# MCU.net
KiCad netlist of a schematic drawn in Altium Designer
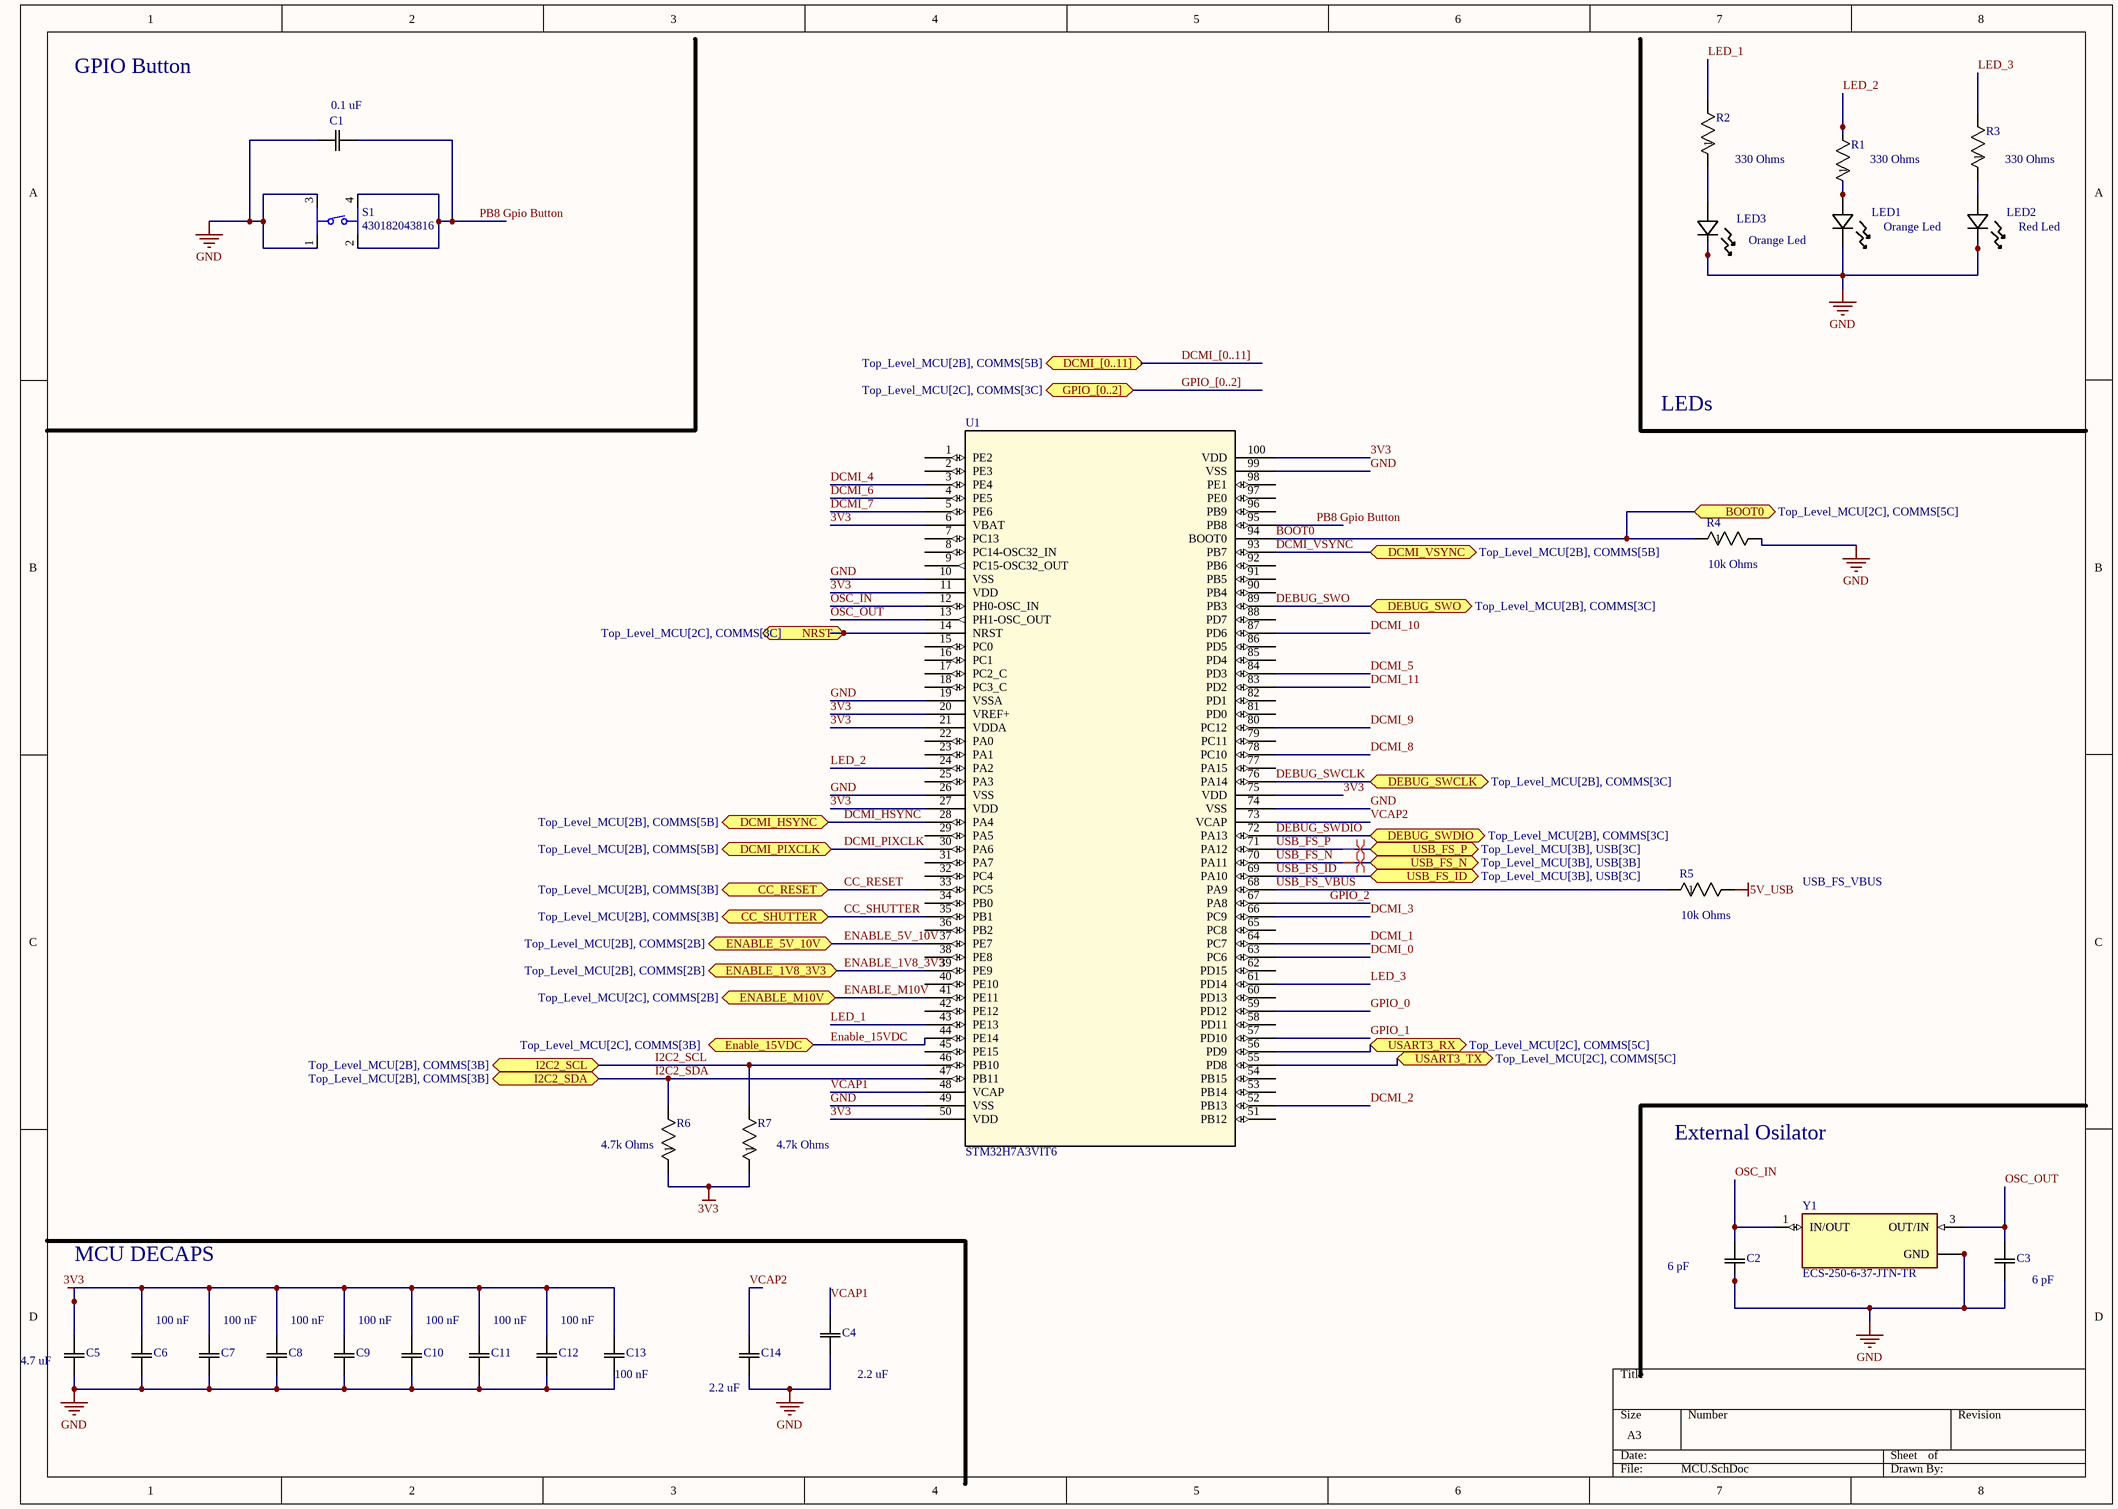
[diagram p0: MCU.SchDoc]

(export (version "E")
  (design (tool "Eeschema 10.0.6"))
  (components
    (comp (ref "C1")
      (value "CC0805KRX7R7BB104")
      (footprint "CC0805N_YAG")
      (description "Description")
      (fields (field (name "COPYRIGHT") "Copyright (C) 2025 Ultra Librarian. All rights reserved."))
      (libsource (lib "CC0805KRX7R7BB104") (part "CC0805KRX7R7BB104"))
    )
    (comp (ref "C2")
      (value "CC0805KRX7R7BB104")
      (footprint "CC0805N_YAG")
      (description "Description")
      (fields (field (name "COPYRIGHT") "Copyright (C) 2025 Ultra Librarian. All rights reserved."))
      (libsource (lib "CC0805KRX7R7BB104") (part "CC0805KRX7R7BB104"))
    )
    (comp (ref "C3")
      (value "CC0805KRX7R7BB104")
      (footprint "CC0805N_YAG")
      (description "Description")
      (fields (field (name "COPYRIGHT") "Copyright (C) 2025 Ultra Librarian. All rights reserved."))
      (libsource (lib "CC0805KRX7R7BB104") (part "CC0805KRX7R7BB104"))
    )
    (comp (ref "C4")
      (value "CC0805KRX7R7BB104")
      (footprint "CC0805N_YAG")
      (description "Description")
      (fields (field (name "COPYRIGHT") "Copyright (C) 2025 Ultra Librarian. All rights reserved."))
      (libsource (lib "CC0805KRX7R7BB104") (part "CC0805KRX7R7BB104"))
    )
    (comp (ref "C5")
      (value "CC0805KRX7R7BB104")
      (footprint "CC0805N_YAG")
      (description "Description")
      (fields (field (name "COPYRIGHT") "Copyright (C) 2025 Ultra Librarian. All rights reserved."))
      (libsource (lib "CC0805KRX7R7BB104") (part "CC0805KRX7R7BB104"))
    )
    (comp (ref "C6")
      (value "CC0805KRX7R7BB104")
      (footprint "CC0805N_YAG")
      (description "Description")
      (fields (field (name "COPYRIGHT") "Copyright (C) 2025 Ultra Librarian. All rights reserved."))
      (libsource (lib "CC0805KRX7R7BB104") (part "CC0805KRX7R7BB104"))
    )
    (comp (ref "C7")
      (value "CC0805KRX7R7BB104")
      (footprint "CC0805N_YAG")
      (description "Description")
      (fields (field (name "COPYRIGHT") "Copyright (C) 2025 Ultra Librarian. All rights reserved."))
      (libsource (lib "CC0805KRX7R7BB104") (part "CC0805KRX7R7BB104"))
    )
    (comp (ref "C8")
      (value "CC0805KRX7R7BB104")
      (footprint "CC0805N_YAG")
      (description "Description")
      (fields (field (name "COPYRIGHT") "Copyright (C) 2025 Ultra Librarian. All rights reserved."))
      (libsource (lib "CC0805KRX7R7BB104") (part "CC0805KRX7R7BB104"))
    )
    (comp (ref "C9")
      (value "CC0805KRX7R7BB104")
      (footprint "CC0805N_YAG")
      (description "Description")
      (fields (field (name "COPYRIGHT") "Copyright (C) 2025 Ultra Librarian. All rights reserved."))
      (libsource (lib "CC0805KRX7R7BB104") (part "CC0805KRX7R7BB104"))
    )
    (comp (ref "C10")
      (value "CC0805KRX7R7BB104")
      (footprint "CC0805N_YAG")
      (description "Description")
      (fields (field (name "COPYRIGHT") "Copyright (C) 2025 Ultra Librarian. All rights reserved."))
      (libsource (lib "CC0805KRX7R7BB104") (part "CC0805KRX7R7BB104"))
    )
    (comp (ref "C11")
      (value "CC0805KRX7R7BB104")
      (footprint "CC0805N_YAG")
      (description "Description")
      (fields (field (name "COPYRIGHT") "Copyright (C) 2025 Ultra Librarian. All rights reserved."))
      (libsource (lib "CC0805KRX7R7BB104") (part "CC0805KRX7R7BB104"))
    )
    (comp (ref "C12")
      (value "CC0805KRX7R7BB104")
      (footprint "CC0805N_YAG")
      (description "Description")
      (fields (field (name "COPYRIGHT") "Copyright (C) 2025 Ultra Librarian. All rights reserved."))
      (libsource (lib "CC0805KRX7R7BB104") (part "CC0805KRX7R7BB104"))
    )
    (comp (ref "C13")
      (value "CC0805KRX7R7BB104")
      (footprint "CC0805N_YAG")
      (description "Description")
      (fields (field (name "COPYRIGHT") "Copyright (C) 2025 Ultra Librarian. All rights reserved."))
      (libsource (lib "CC0805KRX7R7BB104") (part "CC0805KRX7R7BB104"))
    )
    (comp (ref "C14")
      (value "CC0805KRX7R7BB104")
      (footprint "CC0805N_YAG")
      (description "Description")
      (fields (field (name "COPYRIGHT") "Copyright (C) 2025 Ultra Librarian. All rights reserved."))
      (libsource (lib "CC0805KRX7R7BB104") (part "CC0805KRX7R7BB104"))
    )
    (comp (ref "LED1")
      (value "LTST-C170KFKT")
      (footprint "LED_LTST-C170KFKT_LTO")
      (description "Description")
      (fields (field (name "COPYRIGHT") "Copyright (C) 2025 Ultra Librarian. All rights reserved."))
      (libsource (lib "LTST-C170KFKT") (part "LTST-C170KFKT"))
    )
    (comp (ref "LED2")
      (value "LTST-C171KRKT")
      (footprint "LED_LTST-C171_LTO")
      (description "Description")
      (fields (field (name "COPYRIGHT") "Copyright (C) 2025 Ultra Librarian. All rights reserved."))
      (libsource (lib "LTST-C171KRKT") (part "LTST-C171KRKT"))
    )
    (comp (ref "LED3")
      (value "LTST-C170KFKT")
      (footprint "LED_LTST-C170KFKT_LTO")
      (description "Description")
      (fields (field (name "COPYRIGHT") "Copyright (C) 2025 Ultra Librarian. All rights reserved."))
      (libsource (lib "LTST-C170KFKT") (part "LTST-C170KFKT"))
    )
    (comp (ref "R1")
      (value "RC0805FR-074K7L")
      (footprint "RES_RC0805_YAG")
      (description "RES SMD 4.7 k? 1% 1/8W 0805")
      (fields (field (name "COPYRIGHT") "Copyright (C) 2025 Ultra Librarian. All rights reserved."))
      (libsource (lib "RC0805FR-074K7L") (part "RC0805FR-074K7L"))
    )
    (comp (ref "R2")
      (value "RC0805FR-074K7L")
      (footprint "RES_RC0805_YAG")
      (description "RES SMD 4.7 k? 1% 1/8W 0805")
      (fields (field (name "COPYRIGHT") "Copyright (C) 2025 Ultra Librarian. All rights reserved."))
      (libsource (lib "RC0805FR-074K7L") (part "RC0805FR-074K7L"))
    )
    (comp (ref "R3")
      (value "RC0805FR-074K7L")
      (footprint "RES_RC0805_YAG")
      (description "RES SMD 4.7 k? 1% 1/8W 0805")
      (fields (field (name "COPYRIGHT") "Copyright (C) 2025 Ultra Librarian. All rights reserved."))
      (libsource (lib "RC0805FR-074K7L") (part "RC0805FR-074K7L"))
    )
    (comp (ref "R4")
      (value "RC0805FR-074K7L")
      (footprint "RES_RC0805_YAG")
      (description "RES SMD 4.7 k? 1% 1/8W 0805")
      (fields (field (name "COPYRIGHT") "Copyright (C) 2025 Ultra Librarian. All rights reserved."))
      (libsource (lib "RC0805FR-074K7L") (part "RC0805FR-074K7L"))
    )
    (comp (ref "R5")
      (value "RC0805FR-074K7L")
      (footprint "RES_RC0805_YAG")
      (description "RES SMD 4.7 k? 1% 1/8W 0805")
      (fields (field (name "COPYRIGHT") "Copyright (C) 2025 Ultra Librarian. All rights reserved."))
      (libsource (lib "RC0805FR-074K7L") (part "RC0805FR-074K7L"))
    )
    (comp (ref "R6")
      (value "RC0805FR-074K7L")
      (footprint "RES_RC0805_YAG")
      (description "RES SMD 4.7 k? 1% 1/8W 0805")
      (fields (field (name "COPYRIGHT") "Copyright (C) 2025 Ultra Librarian. All rights reserved."))
      (libsource (lib "RC0805FR-074K7L") (part "RC0805FR-074K7L"))
    )
    (comp (ref "R7")
      (value "RC0805FR-074K7L")
      (footprint "RES_RC0805_YAG")
      (description "RES SMD 4.7 k? 1% 1/8W 0805")
      (fields (field (name "COPYRIGHT") "Copyright (C) 2025 Ultra Librarian. All rights reserved."))
      (libsource (lib "RC0805FR-074K7L") (part "RC0805FR-074K7L"))
    )
    (comp (ref "S1")
      (value "430182043816")
      (footprint "430182043816")
      (description "6*6mm vertical type, SMT, height 4.3mm, black actuator, 160gf, T&R")
      (fields (field (name "MF") "Wurth Electronics"))
      (libsource (lib "430182043816") (part "430182043816"))
    )
    (comp (ref "U1")
      (value "STM32H7A3VIT6")
      (footprint "LQFP100")
      (fields (field (name "COPYRIGHT") "Copyright (C) 2025 Ultra Librarian. All rights reserved."))
      (libsource (lib "STM32H7A3VIT6") (part "STM32H7A3VIT6"))
    )
    (comp (ref "Y1")
      (value "ECS-250-6-37-JTN-TR")
      (footprint "XTAL_ECS-250-6-37-JTN-TR")
      (description "SMD Crystal 2.0 x 1.6 x 0.45 mm ceramic package")
      (libsource (lib "ECS-250-6-37-JTN-TR") (part "ECS-250-6-37-JTN-TR"))
    )
  )
  (nets
    (net (code "1") (name "/BOOT0") (class "Default")
      (node (ref "R4") (pin "1") (pinfunction "1_1") (pintype "passive"))
      (node (ref "U1") (pin "94") (pinfunction "BOOT0_94") (pintype "passive"))
    )
    (net (code "2") (name "/CC_RESET") (class "Default")
      (node (ref "U1") (pin "33") (pinfunction "PC5_33") (pintype "bidirectional"))
    )
    (net (code "3") (name "/CC_SHUTTER") (class "Default")
      (node (ref "U1") (pin "35") (pinfunction "PB1_35") (pintype "bidirectional"))
    )
    (net (code "4") (name "/DCMI_0") (class "Default")
      (node (ref "U1") (pin "63") (pinfunction "PC6_63") (pintype "bidirectional"))
    )
    (net (code "5") (name "/DCMI_1") (class "Default")
      (node (ref "U1") (pin "64") (pinfunction "PC7_64") (pintype "bidirectional"))
    )
    (net (code "6") (name "/DCMI_2") (class "Default")
      (node (ref "U1") (pin "52") (pinfunction "PB13_52") (pintype "bidirectional"))
    )
    (net (code "7") (name "/DCMI_3") (class "Default")
      (node (ref "U1") (pin "66") (pinfunction "PC9_66") (pintype "bidirectional"))
    )
    (net (code "8") (name "/DCMI_4") (class "Default")
      (node (ref "U1") (pin "3") (pinfunction "PE4_3") (pintype "bidirectional"))
    )
    (net (code "9") (name "/DCMI_5") (class "Default")
      (node (ref "U1") (pin "84") (pinfunction "PD3_84") (pintype "bidirectional"))
    )
    (net (code "10") (name "/DCMI_6") (class "Default")
      (node (ref "U1") (pin "4") (pinfunction "PE5_4") (pintype "bidirectional"))
    )
    (net (code "11") (name "/DCMI_7") (class "Default")
      (node (ref "U1") (pin "5") (pinfunction "PE6_5") (pintype "bidirectional"))
    )
    (net (code "12") (name "/DCMI_8") (class "Default")
      (node (ref "U1") (pin "78") (pinfunction "PC10_78") (pintype "bidirectional"))
    )
    (net (code "13") (name "/DCMI_9") (class "Default")
      (node (ref "U1") (pin "80") (pinfunction "PC12_80") (pintype "bidirectional"))
    )
    (net (code "14") (name "/DCMI_10") (class "Default")
      (node (ref "U1") (pin "87") (pinfunction "PD6_87") (pintype "bidirectional"))
    )
    (net (code "15") (name "/DCMI_11") (class "Default")
      (node (ref "U1") (pin "83") (pinfunction "PD2_83") (pintype "bidirectional"))
    )
    (net (code "16") (name "/DCMI_HSYNC") (class "Default")
      (node (ref "U1") (pin "28") (pinfunction "PA4_28") (pintype "bidirectional"))
    )
    (net (code "17") (name "/DCMI_PIXCLK") (class "Default")
      (node (ref "U1") (pin "30") (pinfunction "PA6_30") (pintype "bidirectional"))
    )
    (net (code "18") (name "/DCMI_VSYNC") (class "Default")
      (node (ref "U1") (pin "93") (pinfunction "PB7_93") (pintype "bidirectional"))
    )
    (net (code "20") (name "/DEBUG_SWCLK") (class "Default")
      (node (ref "U1") (pin "76") (pinfunction "PA14_76") (pintype "bidirectional"))
    )
    (net (code "21") (name "/DEBUG_SWDIO") (class "Default")
      (node (ref "U1") (pin "72") (pinfunction "PA13_72") (pintype "bidirectional"))
    )
    (net (code "22") (name "/DEBUG_SWO") (class "Default")
      (node (ref "U1") (pin "89") (pinfunction "PB3_89") (pintype "bidirectional"))
    )
    (net (code "23") (name "/ENABLE_1V8_3V3") (class "Default")
      (node (ref "U1") (pin "39") (pinfunction "PE9_39") (pintype "bidirectional"))
    )
    (net (code "24") (name "/ENABLE_5V_10V") (class "Default")
      (node (ref "U1") (pin "37") (pinfunction "PE7_37") (pintype "bidirectional"))
    )
    (net (code "25") (name "/ENABLE_M10V") (class "Default")
      (node (ref "U1") (pin "41") (pinfunction "PE11_41") (pintype "bidirectional"))
    )
    (net (code "26") (name "/Enable_15VDC") (class "Default")
      (node (ref "U1") (pin "44") (pinfunction "PE14_44") (pintype "bidirectional"))
    )
    (net (code "27") (name "/GPIO_0") (class "Default")
      (node (ref "U1") (pin "59") (pinfunction "PD12_59") (pintype "bidirectional"))
    )
    (net (code "28") (name "/GPIO_1") (class "Default")
      (node (ref "U1") (pin "57") (pinfunction "PD10_57") (pintype "bidirectional"))
    )
    (net (code "29") (name "/GPIO_2") (class "Default")
      (node (ref "U1") (pin "67") (pinfunction "PA8_67") (pintype "bidirectional"))
    )
    (net (code "31") (name "/I2C2_SCL") (class "Default")
      (node (ref "R7") (pin "2") (pinfunction "2_2") (pintype "passive"))
      (node (ref "U1") (pin "46") (pinfunction "PB10_46") (pintype "bidirectional"))
    )
    (net (code "32") (name "/I2C2_SDA") (class "Default")
      (node (ref "R6") (pin "2") (pinfunction "2_2") (pintype "passive"))
      (node (ref "U1") (pin "47") (pinfunction "PB11_47") (pintype "bidirectional"))
    )
    (net (code "33") (name "/LED_1") (class "Default")
      (node (ref "R2") (pin "2") (pinfunction "2_2") (pintype "passive"))
      (node (ref "U1") (pin "43") (pinfunction "PE13_43") (pintype "bidirectional"))
    )
    (net (code "34") (name "/LED_2") (class "Default")
      (node (ref "R1") (pin "2") (pinfunction "2_2") (pintype "passive"))
      (node (ref "U1") (pin "24") (pinfunction "PA2_24") (pintype "bidirectional"))
    )
    (net (code "35") (name "/LED_3") (class "Default")
      (node (ref "R3") (pin "2") (pinfunction "2_2") (pintype "passive"))
      (node (ref "U1") (pin "61") (pinfunction "PD14_61") (pintype "bidirectional"))
    )
    (net (code "36") (name "/NRST") (class "Default")
      (node (ref "U1") (pin "14") (pinfunction "NRST_14") (pintype "passive"))
    )
    (net (code "37") (name "/OSC_IN") (class "Default")
      (node (ref "C2") (pin "2") (pinfunction "2_2") (pintype "passive"))
      (node (ref "U1") (pin "12") (pinfunction "PH0-OSC_IN_12") (pintype "bidirectional"))
      (node (ref "Y1") (pin "1") (pinfunction "IN/OUT_1") (pintype "bidirectional"))
    )
    (net (code "38") (name "/OSC_OUT") (class "Default")
      (node (ref "C3") (pin "2") (pinfunction "2_2") (pintype "passive"))
      (node (ref "U1") (pin "13") (pinfunction "PH1-OSC_OUT_13") (pintype "output"))
      (node (ref "Y1") (pin "3") (pinfunction "OUT/IN_3") (pintype "input"))
    )
    (net (code "39") (name "/PB8 Gpio Button") (class "Default")
      (node (ref "C1") (pin "2") (pinfunction "2_2") (pintype "passive"))
      (node (ref "S1") (pin "2") (pinfunction "2_2") (pintype "passive"))
      (node (ref "S1") (pin "4") (pinfunction "4_4") (pintype "passive"))
      (node (ref "U1") (pin "95") (pinfunction "PB8_95") (pintype "bidirectional"))
    )
    (net (code "40") (name "/USART3_RX") (class "Default")
      (node (ref "U1") (pin "56") (pinfunction "PD9_56") (pintype "bidirectional"))
    )
    (net (code "41") (name "/USART3_TX") (class "Default")
      (node (ref "U1") (pin "55") (pinfunction "PD8_55") (pintype "bidirectional"))
    )
    (net (code "42") (name "/USB_FS_ID") (class "Default")
      (node (ref "U1") (pin "69") (pinfunction "PA10_69") (pintype "bidirectional"))
    )
    (net (code "43") (name "/USB_FS_N") (class "Default")
      (node (ref "U1") (pin "70") (pinfunction "PA11_70") (pintype "bidirectional"))
    )
    (net (code "44") (name "/USB_FS_P") (class "Default")
      (node (ref "U1") (pin "71") (pinfunction "PA12_71") (pintype "bidirectional"))
    )
    (net (code "45") (name "/USB_FS_VBUS") (class "Default")
      (node (ref "R5") (pin "1") (pinfunction "1_1") (pintype "passive"))
      (node (ref "U1") (pin "68") (pinfunction "PA9_68") (pintype "bidirectional"))
    )
    (net (code "46") (name "/VCAP1") (class "Default")
      (node (ref "C4") (pin "2") (pinfunction "2_2") (pintype "passive"))
      (node (ref "U1") (pin "48") (pinfunction "VCAP_48") (pintype "passive"))
    )
    (net (code "47") (name "/VCAP2") (class "Default")
      (node (ref "C14") (pin "2") (pinfunction "2_2") (pintype "passive"))
      (node (ref "U1") (pin "73") (pinfunction "VCAP_73") (pintype "passive"))
    )
    (net (code "48") (name "3V3") (class "Default")
      (node (ref "C10") (pin "2") (pinfunction "2_2") (pintype "passive"))
      (node (ref "C11") (pin "2") (pinfunction "2_2") (pintype "passive"))
      (node (ref "C12") (pin "2") (pinfunction "2_2") (pintype "passive"))
      (node (ref "C13") (pin "2") (pinfunction "2_2") (pintype "passive"))
      (node (ref "C5") (pin "2") (pinfunction "2_2") (pintype "passive"))
      (node (ref "C6") (pin "2") (pinfunction "2_2") (pintype "passive"))
      (node (ref "C7") (pin "2") (pinfunction "2_2") (pintype "passive"))
      (node (ref "C8") (pin "2") (pinfunction "2_2") (pintype "passive"))
      (node (ref "C9") (pin "2") (pinfunction "2_2") (pintype "passive"))
      (node (ref "R6") (pin "1") (pinfunction "1_1") (pintype "passive"))
      (node (ref "R7") (pin "1") (pinfunction "1_1") (pintype "passive"))
      (node (ref "U1") (pin "100") (pinfunction "VDD_100") (pintype "power_in"))
      (node (ref "U1") (pin "11") (pinfunction "VDD_11") (pintype "power_in"))
      (node (ref "U1") (pin "20") (pinfunction "VREF+_20") (pintype "power_in"))
      (node (ref "U1") (pin "21") (pinfunction "VDDA_21") (pintype "power_in"))
      (node (ref "U1") (pin "27") (pinfunction "VDD_27") (pintype "power_in"))
      (node (ref "U1") (pin "50") (pinfunction "VDD_50") (pintype "power_in"))
      (node (ref "U1") (pin "6") (pinfunction "VBAT_6") (pintype "passive"))
      (node (ref "U1") (pin "75") (pinfunction "VDD_75") (pintype "power_in"))
    )
    (net (code "49") (name "5V_USB") (class "Default")
      (node (ref "R5") (pin "2") (pinfunction "2_2") (pintype "passive"))
    )
    (net (code "50") (name "GND") (class "Default")
      (node (ref "C1") (pin "1") (pinfunction "1_1") (pintype "passive"))
      (node (ref "C10") (pin "1") (pinfunction "1_1") (pintype "passive"))
      (node (ref "C11") (pin "1") (pinfunction "1_1") (pintype "passive"))
      (node (ref "C12") (pin "1") (pinfunction "1_1") (pintype "passive"))
      (node (ref "C13") (pin "1") (pinfunction "1_1") (pintype "passive"))
      (node (ref "C14") (pin "1") (pinfunction "1_1") (pintype "passive"))
      (node (ref "C2") (pin "1") (pinfunction "1_1") (pintype "passive"))
      (node (ref "C3") (pin "1") (pinfunction "1_1") (pintype "passive"))
      (node (ref "C4") (pin "1") (pinfunction "1_1") (pintype "passive"))
      (node (ref "C5") (pin "1") (pinfunction "1_1") (pintype "passive"))
      (node (ref "C6") (pin "1") (pinfunction "1_1") (pintype "passive"))
      (node (ref "C7") (pin "1") (pinfunction "1_1") (pintype "passive"))
      (node (ref "C8") (pin "1") (pinfunction "1_1") (pintype "passive"))
      (node (ref "C9") (pin "1") (pinfunction "1_1") (pintype "passive"))
      (node (ref "LED1") (pin "1") (pinfunction "1_1") (pintype "passive"))
      (node (ref "LED2") (pin "1") (pinfunction "CATHODE_1") (pintype "passive"))
      (node (ref "LED3") (pin "1") (pinfunction "1_1") (pintype "passive"))
      (node (ref "R4") (pin "2") (pinfunction "2_2") (pintype "passive"))
      (node (ref "S1") (pin "1") (pinfunction "1_1") (pintype "passive"))
      (node (ref "S1") (pin "3") (pinfunction "3_3") (pintype "passive"))
      (node (ref "U1") (pin "10") (pinfunction "VSS_10") (pintype "power_in"))
      (node (ref "U1") (pin "19") (pinfunction "VSSA_19") (pintype "power_in"))
      (node (ref "U1") (pin "26") (pinfunction "VSS_26") (pintype "power_in"))
      (node (ref "U1") (pin "49") (pinfunction "VSS_49") (pintype "power_in"))
      (node (ref "U1") (pin "74") (pinfunction "VSS_74") (pintype "power_in"))
      (node (ref "U1") (pin "99") (pinfunction "VSS_99") (pintype "power_in"))
      (node (ref "Y1") (pin "2") (pinfunction "GND_2") (pintype "power_in"))
      (node (ref "Y1") (pin "4") (pinfunction "GND_4") (pintype "power_in"))
    )
    (net (code "51") (name "Net-(LED1-Pad2)") (class "Default")
      (node (ref "LED1") (pin "2") (pinfunction "2_2") (pintype "passive"))
      (node (ref "R1") (pin "1") (pinfunction "1_1") (pintype "passive"))
    )
    (net (code "52") (name "Net-(LED2-ANODE)") (class "Default")
      (node (ref "LED2") (pin "2") (pinfunction "ANODE_2") (pintype "passive"))
      (node (ref "R3") (pin "1") (pinfunction "1_1") (pintype "passive"))
    )
    (net (code "53") (name "Net-(LED3-Pad2)") (class "Default")
      (node (ref "LED3") (pin "2") (pinfunction "2_2") (pintype "passive"))
      (node (ref "R2") (pin "1") (pinfunction "1_1") (pintype "passive"))
    )
    (net (code "54") (name "unconnected-(U1-PA0-Pad22)") (class "Default")
      (node (ref "U1") (pin "22") (pinfunction "PA0_22") (pintype "bidirectional"))
    )
    (net (code "55") (name "unconnected-(U1-PA1-Pad23)") (class "Default")
      (node (ref "U1") (pin "23") (pinfunction "PA1_23") (pintype "bidirectional"))
    )
    (net (code "56") (name "unconnected-(U1-PA3-Pad25)") (class "Default")
      (node (ref "U1") (pin "25") (pinfunction "PA3_25") (pintype "bidirectional"))
    )
    (net (code "57") (name "unconnected-(U1-PA5-Pad29)") (class "Default")
      (node (ref "U1") (pin "29") (pinfunction "PA5_29") (pintype "bidirectional"))
    )
    (net (code "58") (name "unconnected-(U1-PA7-Pad31)") (class "Default")
      (node (ref "U1") (pin "31") (pinfunction "PA7_31") (pintype "bidirectional"))
    )
    (net (code "59") (name "unconnected-(U1-PA15-Pad77)") (class "Default")
      (node (ref "U1") (pin "77") (pinfunction "PA15_77") (pintype "bidirectional"))
    )
    (net (code "60") (name "unconnected-(U1-PB0-Pad34)") (class "Default")
      (node (ref "U1") (pin "34") (pinfunction "PB0_34") (pintype "bidirectional"))
    )
    (net (code "61") (name "unconnected-(U1-PB2-Pad36)") (class "Default")
      (node (ref "U1") (pin "36") (pinfunction "PB2_36") (pintype "bidirectional"))
    )
    (net (code "62") (name "unconnected-(U1-PB4-Pad90)") (class "Default")
      (node (ref "U1") (pin "90") (pinfunction "PB4_90") (pintype "bidirectional"))
    )
    (net (code "63") (name "unconnected-(U1-PB5-Pad91)") (class "Default")
      (node (ref "U1") (pin "91") (pinfunction "PB5_91") (pintype "bidirectional"))
    )
    (net (code "64") (name "unconnected-(U1-PB6-Pad92)") (class "Default")
      (node (ref "U1") (pin "92") (pinfunction "PB6_92") (pintype "bidirectional"))
    )
    (net (code "65") (name "unconnected-(U1-PB9-Pad96)") (class "Default")
      (node (ref "U1") (pin "96") (pinfunction "PB9_96") (pintype "bidirectional"))
    )
    (net (code "66") (name "unconnected-(U1-PB12-Pad51)") (class "Default")
      (node (ref "U1") (pin "51") (pinfunction "PB12_51") (pintype "bidirectional"))
    )
    (net (code "67") (name "unconnected-(U1-PB14-Pad53)") (class "Default")
      (node (ref "U1") (pin "53") (pinfunction "PB14_53") (pintype "bidirectional"))
    )
    (net (code "68") (name "unconnected-(U1-PB15-Pad54)") (class "Default")
      (node (ref "U1") (pin "54") (pinfunction "PB15_54") (pintype "bidirectional"))
    )
    (net (code "69") (name "unconnected-(U1-PC0-Pad15)") (class "Default")
      (node (ref "U1") (pin "15") (pinfunction "PC0_15") (pintype "bidirectional"))
    )
    (net (code "70") (name "unconnected-(U1-PC1-Pad16)") (class "Default")
      (node (ref "U1") (pin "16") (pinfunction "PC1_16") (pintype "bidirectional"))
    )
    (net (code "71") (name "unconnected-(U1-PC2_C-Pad17)") (class "Default")
      (node (ref "U1") (pin "17") (pinfunction "PC2_C_17") (pintype "bidirectional"))
    )
    (net (code "72") (name "unconnected-(U1-PC3_C-Pad18)") (class "Default")
      (node (ref "U1") (pin "18") (pinfunction "PC3_C_18") (pintype "bidirectional"))
    )
    (net (code "73") (name "unconnected-(U1-PC4-Pad32)") (class "Default")
      (node (ref "U1") (pin "32") (pinfunction "PC4_32") (pintype "bidirectional"))
    )
    (net (code "74") (name "unconnected-(U1-PC8-Pad65)") (class "Default")
      (node (ref "U1") (pin "65") (pinfunction "PC8_65") (pintype "bidirectional"))
    )
    (net (code "75") (name "unconnected-(U1-PC11-Pad79)") (class "Default")
      (node (ref "U1") (pin "79") (pinfunction "PC11_79") (pintype "bidirectional"))
    )
    (net (code "76") (name "unconnected-(U1-PC13-Pad7)") (class "Default")
      (node (ref "U1") (pin "7") (pinfunction "PC13_7") (pintype "bidirectional"))
    )
    (net (code "77") (name "unconnected-(U1-PC14-OSC32_IN-Pad8)") (class "Default")
      (node (ref "U1") (pin "8") (pinfunction "PC14-OSC32_IN_8") (pintype "bidirectional"))
    )
    (net (code "78") (name "unconnected-(U1-PC15-OSC32_OUT-Pad9)") (class "Default")
      (node (ref "U1") (pin "9") (pinfunction "PC15-OSC32_OUT_9") (pintype "output"))
    )
    (net (code "79") (name "unconnected-(U1-PD0-Pad81)") (class "Default")
      (node (ref "U1") (pin "81") (pinfunction "PD0_81") (pintype "bidirectional"))
    )
    (net (code "80") (name "unconnected-(U1-PD1-Pad82)") (class "Default")
      (node (ref "U1") (pin "82") (pinfunction "PD1_82") (pintype "bidirectional"))
    )
    (net (code "81") (name "unconnected-(U1-PD4-Pad85)") (class "Default")
      (node (ref "U1") (pin "85") (pinfunction "PD4_85") (pintype "bidirectional"))
    )
    (net (code "82") (name "unconnected-(U1-PD5-Pad86)") (class "Default")
      (node (ref "U1") (pin "86") (pinfunction "PD5_86") (pintype "bidirectional"))
    )
    (net (code "83") (name "unconnected-(U1-PD7-Pad88)") (class "Default")
      (node (ref "U1") (pin "88") (pinfunction "PD7_88") (pintype "bidirectional"))
    )
    (net (code "84") (name "unconnected-(U1-PD11-Pad58)") (class "Default")
      (node (ref "U1") (pin "58") (pinfunction "PD11_58") (pintype "bidirectional"))
    )
    (net (code "85") (name "unconnected-(U1-PD13-Pad60)") (class "Default")
      (node (ref "U1") (pin "60") (pinfunction "PD13_60") (pintype "bidirectional"))
    )
    (net (code "86") (name "unconnected-(U1-PD15-Pad62)") (class "Default")
      (node (ref "U1") (pin "62") (pinfunction "PD15_62") (pintype "bidirectional"))
    )
    (net (code "87") (name "unconnected-(U1-PE0-Pad97)") (class "Default")
      (node (ref "U1") (pin "97") (pinfunction "PE0_97") (pintype "bidirectional"))
    )
    (net (code "88") (name "unconnected-(U1-PE1-Pad98)") (class "Default")
      (node (ref "U1") (pin "98") (pinfunction "PE1_98") (pintype "bidirectional"))
    )
    (net (code "89") (name "unconnected-(U1-PE2-Pad1)") (class "Default")
      (node (ref "U1") (pin "1") (pinfunction "PE2_1") (pintype "bidirectional"))
    )
    (net (code "90") (name "unconnected-(U1-PE3-Pad2)") (class "Default")
      (node (ref "U1") (pin "2") (pinfunction "PE3_2") (pintype "bidirectional"))
    )
    (net (code "91") (name "unconnected-(U1-PE8-Pad38)") (class "Default")
      (node (ref "U1") (pin "38") (pinfunction "PE8_38") (pintype "bidirectional"))
    )
    (net (code "92") (name "unconnected-(U1-PE10-Pad40)") (class "Default")
      (node (ref "U1") (pin "40") (pinfunction "PE10_40") (pintype "bidirectional"))
    )
    (net (code "93") (name "unconnected-(U1-PE12-Pad42)") (class "Default")
      (node (ref "U1") (pin "42") (pinfunction "PE12_42") (pintype "bidirectional"))
    )
    (net (code "94") (name "unconnected-(U1-PE15-Pad45)") (class "Default")
      (node (ref "U1") (pin "45") (pinfunction "PE15_45") (pintype "bidirectional"))
    )
  )
)
